# danger_danger_psu-mk-4.net
KiCad netlist of a schematic drawn in EAGLE
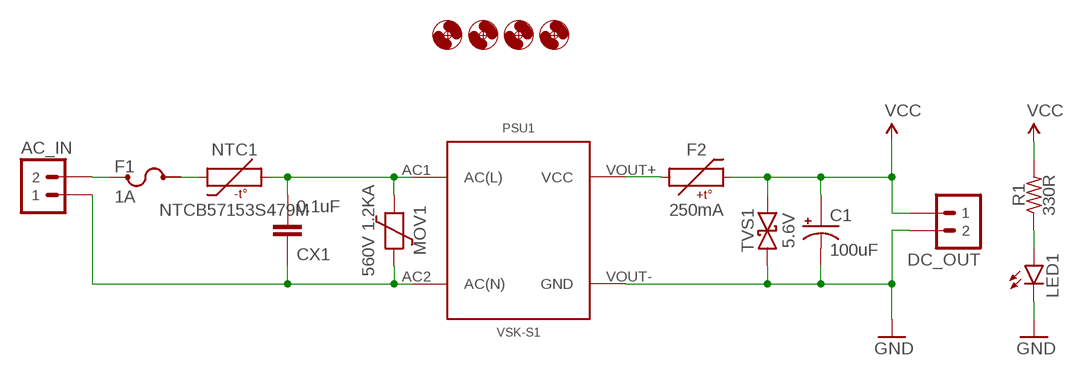
[diagram p0: schematic, sheet 1]

(export (version "E")
  (design (tool "Eeschema 10.0.6"))
  (components
    (comp (ref "AC_IN")
      (value "M023.5MM")
      (footprint "eagle-import:SCREWTERMINAL-3.5MM-2")
      (libsource (lib "eagle-import") (part "M023.5MM"))
    )
    (comp (ref "C1")
      (value "100uF")
      (footprint "eagle-import:E2,5-6")
      (libsource (lib "eagle-import") (part "CAPACITOR-POLARIZEDE2.5-6"))
    )
    (comp (ref "CX1")
      (value "0.1uF")
      (footprint "eagle-import:XC10B6")
      (libsource (lib "eagle-import") (part "CXXC10B6"))
    )
    (comp (ref "DC_OUT")
      (value "M02JST-PTH-VERT")
      (footprint "eagle-import:JST-2-PH-VERT-PTH")
      (libsource (lib "eagle-import") (part "M02JST-PTH-VERT"))
    )
    (comp (ref "F1")
      (value "1A")
      (footprint "eagle-import:TR5")
      (libsource (lib "eagle-import") (part "FUSETR5"))
    )
    (comp (ref "F2")
      (value "250mA")
      (footprint "eagle-import:PTC-PTH-5.08MM")
      (libsource (lib "eagle-import") (part "PTCPTH-5.08MM"))
    )
    (comp (ref "H1")
      (value "HOLE#2")
      (footprint "eagle-import:HOLE-#2")
      (libsource (lib "eagle-import") (part "HOLE#2"))
    )
    (comp (ref "H2")
      (value "HOLE#2")
      (footprint "eagle-import:HOLE-#2")
      (libsource (lib "eagle-import") (part "HOLE#2"))
    )
    (comp (ref "H3")
      (value "HOLE#2")
      (footprint "eagle-import:HOLE-#2")
      (libsource (lib "eagle-import") (part "HOLE#2"))
    )
    (comp (ref "H4")
      (value "HOLE#2")
      (footprint "eagle-import:HOLE-#2")
      (libsource (lib "eagle-import") (part "HOLE#2"))
    )
    (comp (ref "LED1")
      (value "LED3MM")
      (footprint "eagle-import:LED3MM")
      (libsource (lib "eagle-import") (part "LED3MM"))
    )
    (comp (ref "MOV1")
      (value "560V 1.2KA")
      (footprint "eagle-import:VAR-5.08MM-PTH")
      (libsource (lib "eagle-import") (part "VARISITORVAR-5.08MM-PTH"))
    )
    (comp (ref "NTC1")
      (value "NTCB57153S479M")
      (footprint "eagle-import:B57153S479M")
      (libsource (lib "eagle-import") (part "NTCB57153S479M"))
    )
    (comp (ref "PSU1")
      (value "VSK-S1")
      (footprint "eagle-import:VSK-S1")
      (libsource (lib "eagle-import") (part "VSK-S1"))
    )
    (comp (ref "R1")
      (value "330R")
      (footprint "eagle-import:RESISTOR-AXIAL-PTH-5.08MM")
      (libsource (lib "eagle-import") (part "RESISTORPTH-AXIAL-5.08MM"))
    )
    (comp (ref "TVS1")
      (value "5.6V")
      (footprint "eagle-import:DO-41-TVS-BI-10.16MM")
      (libsource (lib "eagle-import") (part "TVSDO-41-10.16MM"))
    )
  )
  (nets
    (net (code "1") (name "GND") (class "Default")
      (node (ref "C1") (pin "-") (pinfunction "-_-") (pintype "passive"))
      (node (ref "DC_OUT") (pin "2") (pinfunction "2_2") (pintype "passive"))
      (node (ref "LED1") (pin "K") (pinfunction "C_K") (pintype "passive"))
      (node (ref "PSU1") (pin "VOUT-") (pinfunction "GND_VOUT-") (pintype "bidirectional"))
      (node (ref "TVS1") (pin "P$2") (pinfunction "2_P$2") (pintype "passive"))
    )
    (net (code "2") (name "Net-(AC_IN-Pad2)") (class "Default")
      (node (ref "AC_IN") (pin "2") (pinfunction "2_2") (pintype "passive"))
      (node (ref "F1") (pin "1") (pinfunction "1_1") (pintype "passive"))
    )
    (net (code "3") (name "Net-(F2-1)") (class "Default")
      (node (ref "F2") (pin "P$1") (pinfunction "1_P$1") (pintype "passive"))
      (node (ref "PSU1") (pin "VOUT+") (pinfunction "VCC_VOUT+") (pintype "bidirectional"))
    )
    (net (code "4") (name "Net-(MOV1-P$1)") (class "Default")
      (node (ref "CX1") (pin "2") (pinfunction "2_2") (pintype "passive"))
      (node (ref "MOV1") (pin "1") (pinfunction "P$1_1") (pintype "passive"))
      (node (ref "NTC1") (pin "2") (pinfunction "P$2_2") (pintype "passive"))
      (node (ref "PSU1") (pin "AC1") (pinfunction "AC(L)_AC1") (pintype "bidirectional"))
    )
    (net (code "5") (name "Net-(MOV1-P$2)") (class "Default")
      (node (ref "AC_IN") (pin "1") (pinfunction "1_1") (pintype "passive"))
      (node (ref "CX1") (pin "1") (pinfunction "1_1") (pintype "passive"))
      (node (ref "MOV1") (pin "2") (pinfunction "P$2_2") (pintype "passive"))
      (node (ref "PSU1") (pin "AC2") (pinfunction "AC(N)_AC2") (pintype "bidirectional"))
    )
    (net (code "6") (name "Net-(NTC1-P$1)") (class "Default")
      (node (ref "F1") (pin "2") (pinfunction "2_2") (pintype "passive"))
      (node (ref "NTC1") (pin "1") (pinfunction "P$1_1") (pintype "passive"))
    )
    (net (code "7") (name "Net-(R1-1)") (class "Default")
      (node (ref "LED1") (pin "A") (pinfunction "A_A") (pintype "passive"))
      (node (ref "R1") (pin "P$1") (pinfunction "1_P$1") (pintype "passive"))
    )
    (net (code "8") (name "VCC") (class "Default")
      (node (ref "C1") (pin "+") (pinfunction "+_+") (pintype "passive"))
      (node (ref "DC_OUT") (pin "1") (pinfunction "1_1") (pintype "passive"))
      (node (ref "F2") (pin "P$2") (pinfunction "2_P$2") (pintype "passive"))
      (node (ref "R1") (pin "P$2") (pinfunction "2_P$2") (pintype "passive"))
      (node (ref "TVS1") (pin "P$1") (pinfunction "1_P$1") (pintype "passive"))
    )
  )
)
